# Tiny_UniProg.net
KiCad netlist of a schematic drawn in EAGLE
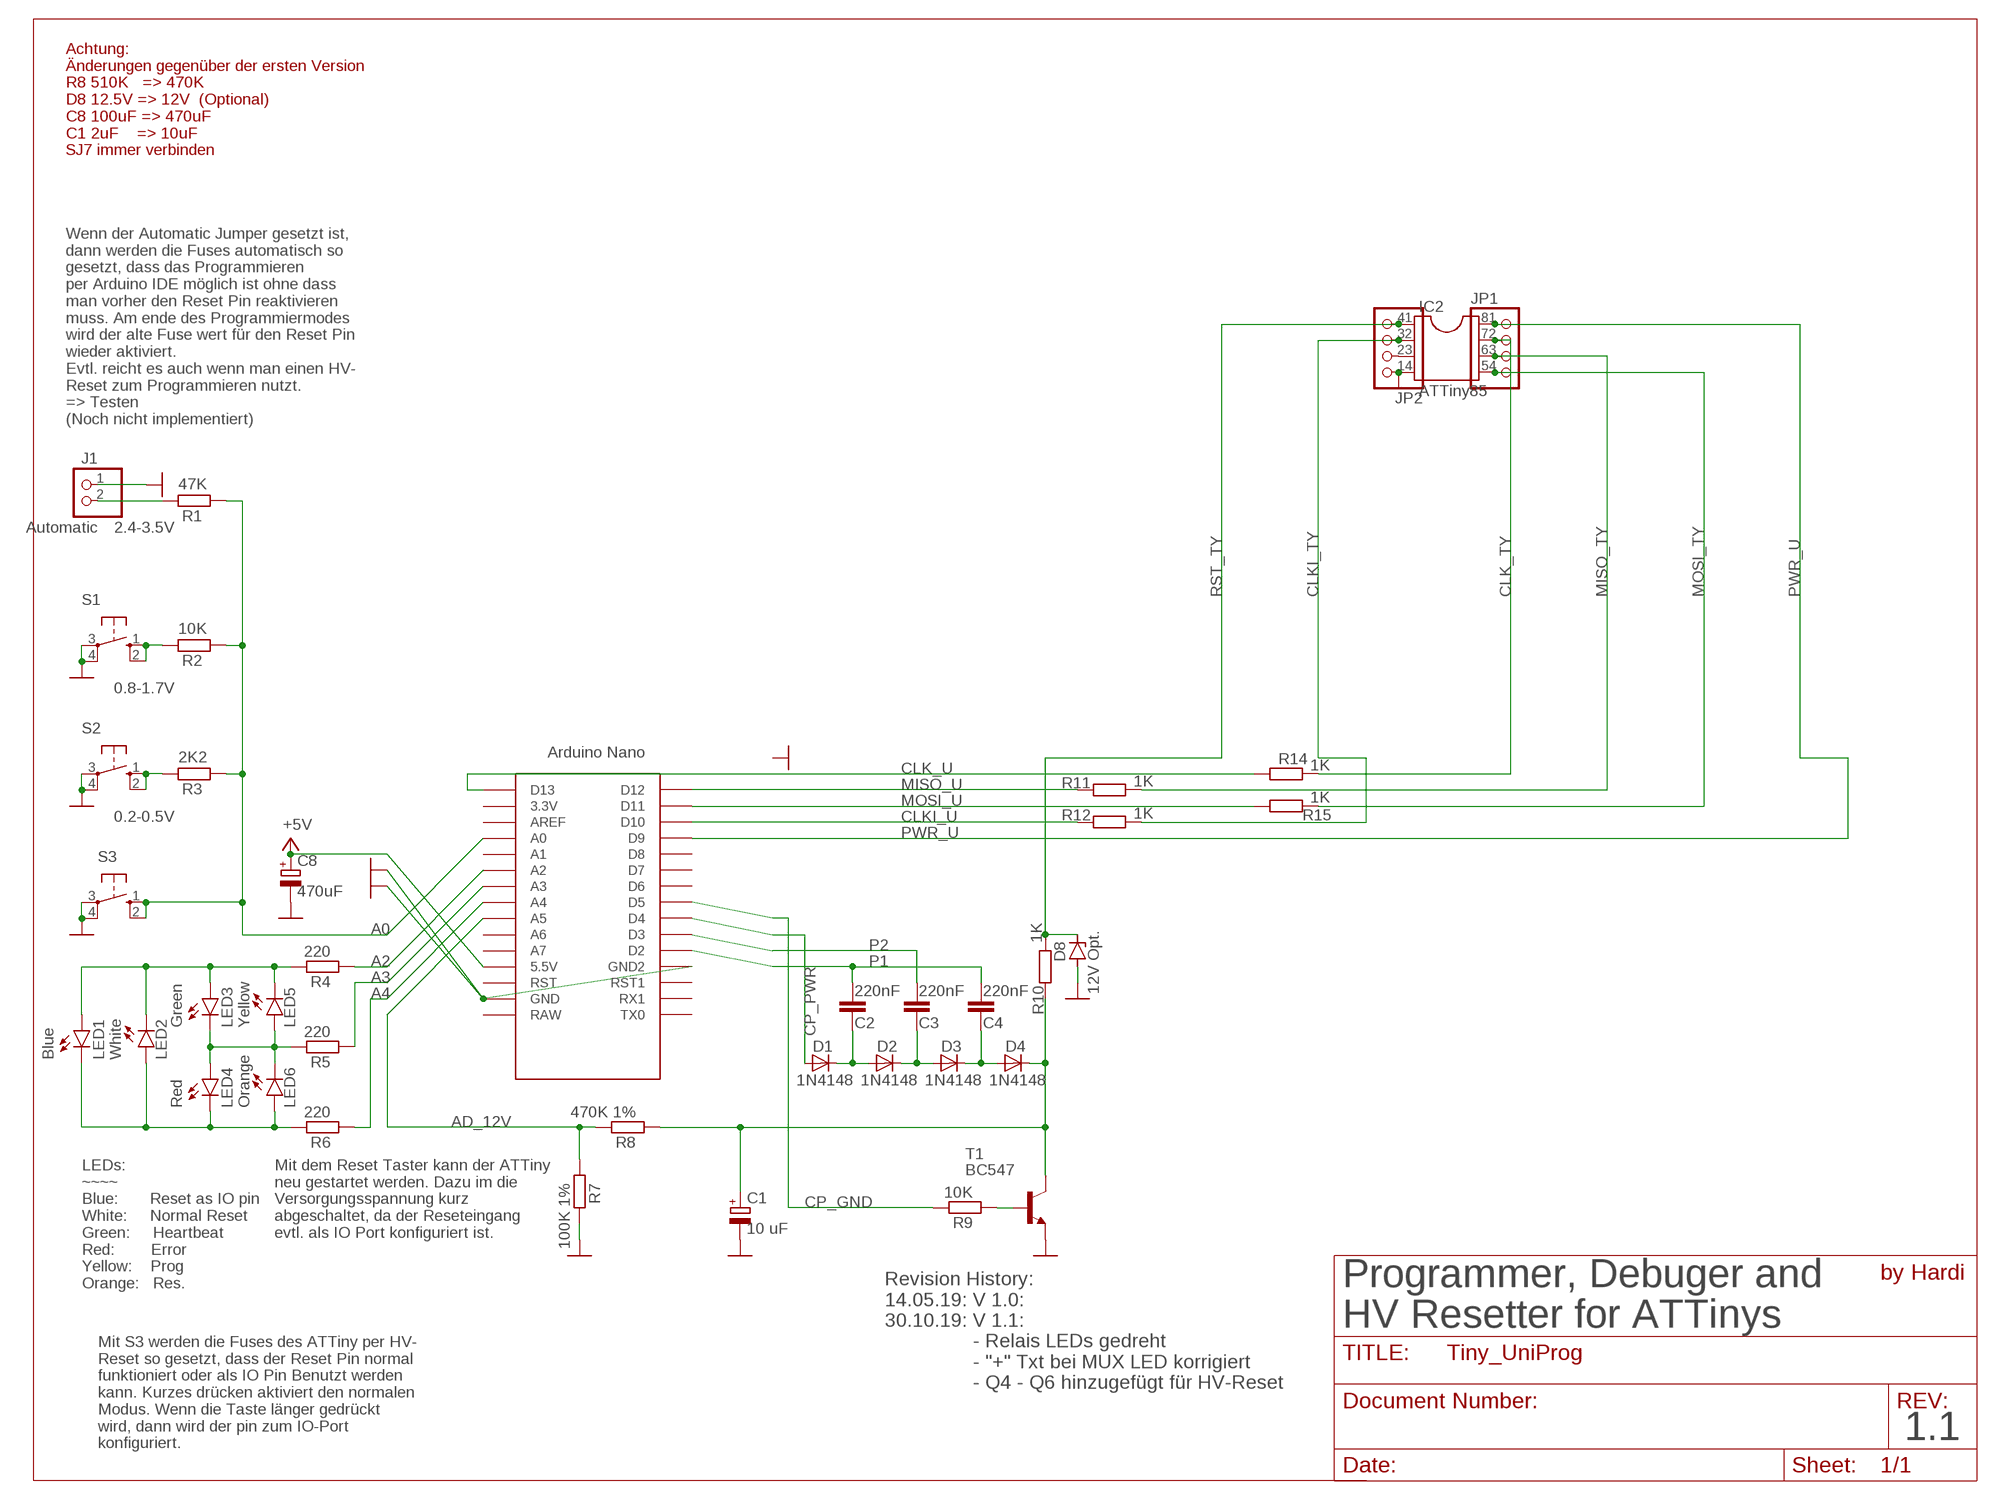
[diagram p0: schematic, sheet 1]

(export (version "E")
  (design (tool "Eeschema 10.0.6"))
  (components
    (comp (ref "C1")
      (value "10 uF")
      (footprint "eagle-import:E5-5")
      (libsource (lib "eagle-import") (part "CPOL-EUE5-5"))
    )
    (comp (ref "C2")
      (value "220nF")
      (footprint "eagle-import:C050-024X044")
      (libsource (lib "eagle-import") (part "C-EU050-024X044"))
    )
    (comp (ref "C3")
      (value "220nF")
      (footprint "eagle-import:C050-024X044")
      (libsource (lib "eagle-import") (part "C-EU050-024X044"))
    )
    (comp (ref "C4")
      (value "220nF")
      (footprint "eagle-import:C050-024X044")
      (libsource (lib "eagle-import") (part "C-EU050-024X044"))
    )
    (comp (ref "C8")
      (value "470uF")
      (footprint "eagle-import:E5-10,5")
      (libsource (lib "eagle-import") (part "CPOL-EUE5-10.5"))
    )
    (comp (ref "D1")
      (value "1N4148")
      (footprint "eagle-import:DO35-2")
      (libsource (lib "eagle-import") (part "1N4148DO35-2"))
    )
    (comp (ref "D2")
      (value "1N4148")
      (footprint "eagle-import:DO35-2")
      (libsource (lib "eagle-import") (part "1N4148DO35-2"))
    )
    (comp (ref "D3")
      (value "1N4148")
      (footprint "eagle-import:DO35-2")
      (libsource (lib "eagle-import") (part "1N4148DO35-2"))
    )
    (comp (ref "D4")
      (value "1N4148")
      (footprint "eagle-import:DO35-2")
      (libsource (lib "eagle-import") (part "1N4148DO35-2"))
    )
    (comp (ref "D8")
      (value "12V Opt.")
      (footprint "eagle-import:ZDIO-2.5")
      (libsource (lib "eagle-import") (part "ZENER-DIODEZD-2.5"))
    )
    (comp (ref "IC2")
      (value "ATTiny85")
      (footprint "eagle-import:DIL08")
      (libsource (lib "eagle-import") (part "DIL8"))
    )
    (comp (ref "J1")
      (value "Automatic")
      (footprint "eagle-import:1X02")
      (libsource (lib "eagle-import") (part "PINHD-1X2"))
    )
    (comp (ref "JP1")
      (value "PINHD-1X4")
      (footprint "eagle-import:1X04")
      (libsource (lib "eagle-import") (part "PINHD-1X4"))
    )
    (comp (ref "JP2")
      (value "PINHD-1X4")
      (footprint "eagle-import:1X04")
      (libsource (lib "eagle-import") (part "PINHD-1X4"))
    )
    (comp (ref "LED1")
      (value "Blue")
      (footprint "eagle-import:LED3MM")
      (libsource (lib "eagle-import") (part "LED3MM"))
    )
    (comp (ref "LED2")
      (value "White")
      (footprint "eagle-import:LED3MM")
      (libsource (lib "eagle-import") (part "LED3MM"))
    )
    (comp (ref "LED3")
      (value "Green")
      (footprint "eagle-import:LED3MM")
      (libsource (lib "eagle-import") (part "LED3MM"))
    )
    (comp (ref "LED4")
      (value "Red")
      (footprint "eagle-import:LED3MM")
      (libsource (lib "eagle-import") (part "LED3MM"))
    )
    (comp (ref "LED5")
      (value "Yellow")
      (footprint "eagle-import:LED3MM")
      (libsource (lib "eagle-import") (part "LED3MM"))
    )
    (comp (ref "LED6")
      (value "Orange")
      (footprint "eagle-import:LED3MM")
      (libsource (lib "eagle-import") (part "LED3MM"))
    )
    (comp (ref "R1")
      (value "47K")
      (footprint "eagle-import:0204V")
      (libsource (lib "eagle-import") (part "R-EU_0204/2V"))
    )
    (comp (ref "R2")
      (value "10K")
      (footprint "eagle-import:0204V")
      (libsource (lib "eagle-import") (part "R-EU_0204/2V"))
    )
    (comp (ref "R3")
      (value "2K2")
      (footprint "eagle-import:0204V")
      (libsource (lib "eagle-import") (part "R-EU_0204/2V"))
    )
    (comp (ref "R4")
      (value "220")
      (footprint "eagle-import:0204_5")
      (libsource (lib "eagle-import") (part "R-EU_0204/5"))
    )
    (comp (ref "R5")
      (value "220")
      (footprint "eagle-import:0204V")
      (libsource (lib "eagle-import") (part "R-EU_0204/2V"))
    )
    (comp (ref "R6")
      (value "220")
      (footprint "eagle-import:0204_5")
      (libsource (lib "eagle-import") (part "R-EU_0204/5"))
    )
    (comp (ref "R7")
      (value "100K 1%")
      (footprint "eagle-import:0204_7")
      (libsource (lib "eagle-import") (part "R-EU_0204/7"))
    )
    (comp (ref "R8")
      (value "470K 1%")
      (footprint "eagle-import:0204V")
      (libsource (lib "eagle-import") (part "R-EU_0204/2V"))
    )
    (comp (ref "R9")
      (value "10K")
      (footprint "eagle-import:0207_12")
      (libsource (lib "eagle-import") (part "R-EU_0207/12"))
    )
    (comp (ref "R10")
      (value "1K")
      (footprint "eagle-import:0204V")
      (libsource (lib "eagle-import") (part "R-EU_0204/2V"))
    )
    (comp (ref "R11")
      (value "1K")
      (footprint "eagle-import:0204V")
      (libsource (lib "eagle-import") (part "R-EU_0204/2V"))
    )
    (comp (ref "R12")
      (value "1K")
      (footprint "eagle-import:0204_5")
      (libsource (lib "eagle-import") (part "R-EU_0204/5"))
    )
    (comp (ref "R14")
      (value "1K")
      (footprint "eagle-import:0207_12")
      (libsource (lib "eagle-import") (part "R-EU_0207/12"))
    )
    (comp (ref "R15")
      (value "1K")
      (footprint "eagle-import:0204_5")
      (libsource (lib "eagle-import") (part "R-EU_0204/5"))
    )
    (comp (ref "S1")
      (value "10-XX")
      (footprint "eagle-import:B3F-10XX")
      (fields (field (name "MPN") "B3F-1000"))
      (libsource (lib "eagle-import") (part "10-XX"))
    )
    (comp (ref "S2")
      (value "10-XX")
      (footprint "eagle-import:B3F-10XX")
      (fields (field (name "MPN") "B3F-1000"))
      (libsource (lib "eagle-import") (part "10-XX"))
    )
    (comp (ref "S3")
      (value "10-XX")
      (footprint "eagle-import:B3F-10XX")
      (fields (field (name "MPN") "B3F-1000"))
      (libsource (lib "eagle-import") (part "10-XX"))
    )
    (comp (ref "T1")
      (value "BC547")
      (footprint "eagle-import:TO92")
      (libsource (lib "eagle-import") (part "BC547"))
    )
    (comp (ref "U$1")
      (value "NANO")
      (footprint "eagle-import:NANO")
      (libsource (lib "eagle-import") (part "NANO"))
    )
  )
  (nets
    (net (code "1") (name "+5V") (class "Default")
      (node (ref "C8") (pin "+") (pinfunction "+_+") (pintype "passive"))
      (node (ref "U$1") (pin "5V") (pinfunction "5.5V_5V") (pintype "bidirectional"))
    )
    (net (code "2") (name "/A0") (class "Default")
      (node (ref "R1") (pin "1") (pinfunction "1_1") (pintype "passive"))
      (node (ref "R2") (pin "1") (pinfunction "1_1") (pintype "passive"))
      (node (ref "R3") (pin "1") (pinfunction "1_1") (pintype "passive"))
      (node (ref "S3") (pin "1") (pinfunction "S_1") (pintype "passive"))
      (node (ref "S3") (pin "2") (pinfunction "S1_2") (pintype "passive"))
      (node (ref "U$1") (pin "A0") (pinfunction "A0_A0") (pintype "bidirectional"))
    )
    (net (code "3") (name "/A2") (class "Default")
      (node (ref "R4") (pin "1") (pinfunction "1_1") (pintype "passive"))
      (node (ref "U$1") (pin "A2") (pinfunction "A2_A2") (pintype "bidirectional"))
    )
    (net (code "4") (name "/A3") (class "Default")
      (node (ref "R5") (pin "1") (pinfunction "1_1") (pintype "passive"))
      (node (ref "U$1") (pin "A3") (pinfunction "A3_A3") (pintype "bidirectional"))
    )
    (net (code "5") (name "/A4") (class "Default")
      (node (ref "R6") (pin "1") (pinfunction "1_1") (pintype "passive"))
      (node (ref "U$1") (pin "A4") (pinfunction "A4_A4") (pintype "bidirectional"))
    )
    (net (code "6") (name "/AD_12V") (class "Default")
      (node (ref "R7") (pin "1") (pinfunction "1_1") (pintype "passive"))
      (node (ref "R8") (pin "2") (pinfunction "2_2") (pintype "passive"))
      (node (ref "U$1") (pin "A5") (pinfunction "A5_A5") (pintype "bidirectional"))
    )
    (net (code "7") (name "/CLKI_TY") (class "Default")
      (node (ref "IC2") (pin "2") (pinfunction "2_2") (pintype "passive"))
      (node (ref "JP2") (pin "3") (pinfunction "3_3") (pintype "passive"))
      (node (ref "R12") (pin "2") (pinfunction "2_2") (pintype "passive"))
    )
    (net (code "8") (name "/CLKI_U") (class "Default")
      (node (ref "R12") (pin "1") (pinfunction "1_1") (pintype "passive"))
      (node (ref "U$1") (pin "D10") (pinfunction "D10_D10") (pintype "bidirectional"))
    )
    (net (code "9") (name "/CLK_TY") (class "Default")
      (node (ref "IC2") (pin "7") (pinfunction "7_7") (pintype "passive"))
      (node (ref "JP1") (pin "2") (pinfunction "2_2") (pintype "passive"))
      (node (ref "R14") (pin "2") (pinfunction "2_2") (pintype "passive"))
    )
    (net (code "10") (name "/CLK_U") (class "Default")
      (node (ref "R14") (pin "1") (pinfunction "1_1") (pintype "passive"))
      (node (ref "U$1") (pin "D13") (pinfunction "D13_D13") (pintype "bidirectional"))
    )
    (net (code "11") (name "/CP_GND") (class "Default")
      (node (ref "R9") (pin "2") (pinfunction "2_2") (pintype "passive"))
      (node (ref "U$1") (pin "D5") (pinfunction "D5_D5") (pintype "bidirectional"))
    )
    (net (code "12") (name "/CP_PWR") (class "Default")
      (node (ref "D1") (pin "A") (pinfunction "A_A") (pintype "passive"))
      (node (ref "U$1") (pin "D4") (pinfunction "D4_D4") (pintype "bidirectional"))
    )
    (net (code "13") (name "/MISO_TY") (class "Default")
      (node (ref "IC2") (pin "6") (pinfunction "6_6") (pintype "passive"))
      (node (ref "JP1") (pin "3") (pinfunction "3_3") (pintype "passive"))
      (node (ref "R11") (pin "2") (pinfunction "2_2") (pintype "passive"))
    )
    (net (code "14") (name "/MISO_U") (class "Default")
      (node (ref "R11") (pin "1") (pinfunction "1_1") (pintype "passive"))
      (node (ref "U$1") (pin "D12") (pinfunction "D12_D12") (pintype "bidirectional"))
    )
    (net (code "15") (name "/MOSI_TY") (class "Default")
      (node (ref "IC2") (pin "5") (pinfunction "5_5") (pintype "passive"))
      (node (ref "JP1") (pin "4") (pinfunction "4_4") (pintype "passive"))
      (node (ref "R15") (pin "2") (pinfunction "2_2") (pintype "passive"))
    )
    (net (code "16") (name "/MOSI_U") (class "Default")
      (node (ref "R15") (pin "1") (pinfunction "1_1") (pintype "passive"))
      (node (ref "U$1") (pin "D11") (pinfunction "D11_D11") (pintype "bidirectional"))
    )
    (net (code "17") (name "/P1") (class "Default")
      (node (ref "C2") (pin "1") (pinfunction "1_1") (pintype "passive"))
      (node (ref "C4") (pin "1") (pinfunction "1_1") (pintype "passive"))
      (node (ref "U$1") (pin "D2") (pinfunction "D2_D2") (pintype "bidirectional"))
    )
    (net (code "18") (name "/P2") (class "Default")
      (node (ref "C3") (pin "1") (pinfunction "1_1") (pintype "passive"))
      (node (ref "U$1") (pin "D3") (pinfunction "D3_D3") (pintype "bidirectional"))
    )
    (net (code "19") (name "/PWR_U") (class "Default")
      (node (ref "IC2") (pin "8") (pinfunction "8_8") (pintype "passive"))
      (node (ref "JP1") (pin "1") (pinfunction "1_1") (pintype "passive"))
      (node (ref "U$1") (pin "D9") (pinfunction "D9_D9") (pintype "bidirectional"))
    )
    (net (code "20") (name "/RST_TY") (class "Default")
      (node (ref "D8") (pin "C") (pinfunction "C_C") (pintype "passive"))
      (node (ref "IC2") (pin "1") (pinfunction "1_1") (pintype "passive"))
      (node (ref "JP2") (pin "4") (pinfunction "4_4") (pintype "passive"))
      (node (ref "R10") (pin "1") (pinfunction "1_1") (pintype "passive"))
    )
    (net (code "21") (name "GND") (class "Default")
      (node (ref "C1") (pin "-") (pinfunction "-_-") (pintype "passive"))
      (node (ref "C8") (pin "-") (pinfunction "-_-") (pintype "passive"))
      (node (ref "D8") (pin "A") (pinfunction "A_A") (pintype "passive"))
      (node (ref "IC2") (pin "4") (pinfunction "4_4") (pintype "passive"))
      (node (ref "J1") (pin "1") (pinfunction "1_1") (pintype "passive"))
      (node (ref "JP2") (pin "1") (pinfunction "1_1") (pintype "passive"))
      (node (ref "R7") (pin "2") (pinfunction "2_2") (pintype "passive"))
      (node (ref "S1") (pin "3") (pinfunction "P_3") (pintype "passive"))
      (node (ref "S1") (pin "4") (pinfunction "P1_4") (pintype "passive"))
      (node (ref "S2") (pin "3") (pinfunction "P_3") (pintype "passive"))
      (node (ref "S2") (pin "4") (pinfunction "P1_4") (pintype "passive"))
      (node (ref "S3") (pin "3") (pinfunction "P_3") (pintype "passive"))
      (node (ref "S3") (pin "4") (pinfunction "P1_4") (pintype "passive"))
      (node (ref "T1") (pin "1") (pinfunction "E_1") (pintype "passive"))
      (node (ref "U$1") (pin "GND") (pinfunction "GND_GND") (pintype "bidirectional"))
      (node (ref "U$1") (pin "GND1") (pinfunction "GND2_GND1") (pintype "bidirectional"))
    )
    (net (code "22") (name "Net-(C2-Pad2)") (class "Default")
      (node (ref "C2") (pin "2") (pinfunction "2_2") (pintype "passive"))
      (node (ref "D1") (pin "C") (pinfunction "C_C") (pintype "passive"))
      (node (ref "D2") (pin "A") (pinfunction "A_A") (pintype "passive"))
    )
    (net (code "23") (name "Net-(C3-Pad2)") (class "Default")
      (node (ref "C3") (pin "2") (pinfunction "2_2") (pintype "passive"))
      (node (ref "D2") (pin "C") (pinfunction "C_C") (pintype "passive"))
      (node (ref "D3") (pin "A") (pinfunction "A_A") (pintype "passive"))
    )
    (net (code "24") (name "Net-(C4-Pad2)") (class "Default")
      (node (ref "C4") (pin "2") (pinfunction "2_2") (pintype "passive"))
      (node (ref "D3") (pin "C") (pinfunction "C_C") (pintype "passive"))
      (node (ref "D4") (pin "A") (pinfunction "A_A") (pintype "passive"))
    )
    (net (code "25") (name "Net-(IC2-Pad3)") (class "Default")
      (node (ref "IC2") (pin "3") (pinfunction "3_3") (pintype "passive"))
      (node (ref "JP2") (pin "2") (pinfunction "2_2") (pintype "passive"))
    )
    (net (code "26") (name "Net-(J1-Pad2)") (class "Default")
      (node (ref "J1") (pin "2") (pinfunction "2_2") (pintype "passive"))
      (node (ref "R1") (pin "2") (pinfunction "2_2") (pintype "passive"))
    )
    (net (code "27") (name "Net-(LED1-C)") (class "Default")
      (node (ref "LED1") (pin "K") (pinfunction "C_K") (pintype "passive"))
      (node (ref "LED2") (pin "A") (pinfunction "A_A") (pintype "passive"))
      (node (ref "LED4") (pin "K") (pinfunction "C_K") (pintype "passive"))
      (node (ref "LED6") (pin "A") (pinfunction "A_A") (pintype "passive"))
      (node (ref "R6") (pin "2") (pinfunction "2_2") (pintype "passive"))
    )
    (net (code "28") (name "Net-(LED2-C)") (class "Default")
      (node (ref "LED1") (pin "A") (pinfunction "A_A") (pintype "passive"))
      (node (ref "LED2") (pin "K") (pinfunction "C_K") (pintype "passive"))
      (node (ref "LED3") (pin "A") (pinfunction "A_A") (pintype "passive"))
      (node (ref "LED5") (pin "K") (pinfunction "C_K") (pintype "passive"))
      (node (ref "R4") (pin "2") (pinfunction "2_2") (pintype "passive"))
    )
    (net (code "29") (name "Net-(LED3-C)") (class "Default")
      (node (ref "LED3") (pin "K") (pinfunction "C_K") (pintype "passive"))
      (node (ref "LED4") (pin "A") (pinfunction "A_A") (pintype "passive"))
      (node (ref "LED5") (pin "A") (pinfunction "A_A") (pintype "passive"))
      (node (ref "LED6") (pin "K") (pinfunction "C_K") (pintype "passive"))
      (node (ref "R5") (pin "2") (pinfunction "2_2") (pintype "passive"))
    )
    (net (code "30") (name "Net-(S1-S)") (class "Default")
      (node (ref "R2") (pin "2") (pinfunction "2_2") (pintype "passive"))
      (node (ref "S1") (pin "1") (pinfunction "S_1") (pintype "passive"))
      (node (ref "S1") (pin "2") (pinfunction "S1_2") (pintype "passive"))
    )
    (net (code "31") (name "Net-(S2-S)") (class "Default")
      (node (ref "R3") (pin "2") (pinfunction "2_2") (pintype "passive"))
      (node (ref "S2") (pin "1") (pinfunction "S_1") (pintype "passive"))
      (node (ref "S2") (pin "2") (pinfunction "S1_2") (pintype "passive"))
    )
    (net (code "32") (name "Net-(T1-B)") (class "Default")
      (node (ref "R9") (pin "1") (pinfunction "1_1") (pintype "passive"))
      (node (ref "T1") (pin "2") (pinfunction "B_2") (pintype "passive"))
    )
    (net (code "33") (name "Net-(T1-C)") (class "Default")
      (node (ref "C1") (pin "+") (pinfunction "+_+") (pintype "passive"))
      (node (ref "D4") (pin "C") (pinfunction "C_C") (pintype "passive"))
      (node (ref "R10") (pin "2") (pinfunction "2_2") (pintype "passive"))
      (node (ref "R8") (pin "1") (pinfunction "1_1") (pintype "passive"))
      (node (ref "T1") (pin "3") (pinfunction "C_3") (pintype "passive"))
    )
    (net (code "34") (name "unconnected-(U$1-Pad3.3V)") (class "Default")
      (node (ref "U$1") (pin "3.3V") (pinfunction "3.3V_3.3V") (pintype "bidirectional"))
    )
    (net (code "35") (name "unconnected-(U$1-PadA1)") (class "Default")
      (node (ref "U$1") (pin "A1") (pinfunction "A1_A1") (pintype "bidirectional"))
    )
    (net (code "36") (name "unconnected-(U$1-PadA6)") (class "Default")
      (node (ref "U$1") (pin "A6") (pinfunction "A6_A6") (pintype "bidirectional"))
    )
    (net (code "37") (name "unconnected-(U$1-PadA7)") (class "Default")
      (node (ref "U$1") (pin "A7") (pinfunction "A7_A7") (pintype "bidirectional"))
    )
    (net (code "38") (name "unconnected-(U$1-PadAREF)") (class "Default")
      (node (ref "U$1") (pin "AREF") (pinfunction "AREF_AREF") (pintype "bidirectional"))
    )
    (net (code "39") (name "unconnected-(U$1-PadD6)") (class "Default")
      (node (ref "U$1") (pin "D6") (pinfunction "D6_D6") (pintype "bidirectional"))
    )
    (net (code "40") (name "unconnected-(U$1-PadD7)") (class "Default")
      (node (ref "U$1") (pin "D7") (pinfunction "D7_D7") (pintype "bidirectional"))
    )
    (net (code "41") (name "unconnected-(U$1-PadD8)") (class "Default")
      (node (ref "U$1") (pin "D8") (pinfunction "D8_D8") (pintype "bidirectional"))
    )
    (net (code "42") (name "unconnected-(U$1-PadICSP1)") (class "Default")
      (node (ref "U$1") (pin "ICSP1") (pinfunction "ICSP1_ICSP1") (pintype "bidirectional"))
    )
    (net (code "43") (name "unconnected-(U$1-PadICSP2)") (class "Default")
      (node (ref "U$1") (pin "ICSP2") (pinfunction "ICSP2_ICSP2") (pintype "bidirectional"))
    )
    (net (code "44") (name "unconnected-(U$1-PadICSP3)") (class "Default")
      (node (ref "U$1") (pin "ICSP3") (pinfunction "ICSP3_ICSP3") (pintype "bidirectional"))
    )
    (net (code "45") (name "unconnected-(U$1-PadICSP4)") (class "Default")
      (node (ref "U$1") (pin "ICSP4") (pinfunction "ICSP4_ICSP4") (pintype "bidirectional"))
    )
    (net (code "46") (name "unconnected-(U$1-PadICSP5)") (class "Default")
      (node (ref "U$1") (pin "ICSP5") (pinfunction "ICSP5_ICSP5") (pintype "bidirectional"))
    )
    (net (code "47") (name "unconnected-(U$1-PadICSP6)") (class "Default")
      (node (ref "U$1") (pin "ICSP6") (pinfunction "ICSP6_ICSP6") (pintype "bidirectional"))
    )
    (net (code "48") (name "unconnected-(U$1-PadRAW)") (class "Default")
      (node (ref "U$1") (pin "RAW") (pinfunction "RAW_RAW") (pintype "bidirectional"))
    )
    (net (code "49") (name "unconnected-(U$1-PadRST)") (class "Default")
      (node (ref "U$1") (pin "RST") (pinfunction "RST_RST") (pintype "bidirectional"))
    )
    (net (code "50") (name "unconnected-(U$1-PadRST1)") (class "Default")
      (node (ref "U$1") (pin "RST1") (pinfunction "RST1_RST1") (pintype "bidirectional"))
    )
    (net (code "51") (name "unconnected-(U$1-PadRX1)") (class "Default")
      (node (ref "U$1") (pin "RX1") (pinfunction "RX1_RX1") (pintype "bidirectional"))
    )
    (net (code "52") (name "unconnected-(U$1-PadTX0)") (class "Default")
      (node (ref "U$1") (pin "TX0") (pinfunction "TX0_TX0") (pintype "bidirectional"))
    )
  )
)
